# nrf52_watch_rev_0_9.net
KiCad netlist of a schematic drawn in EAGLE
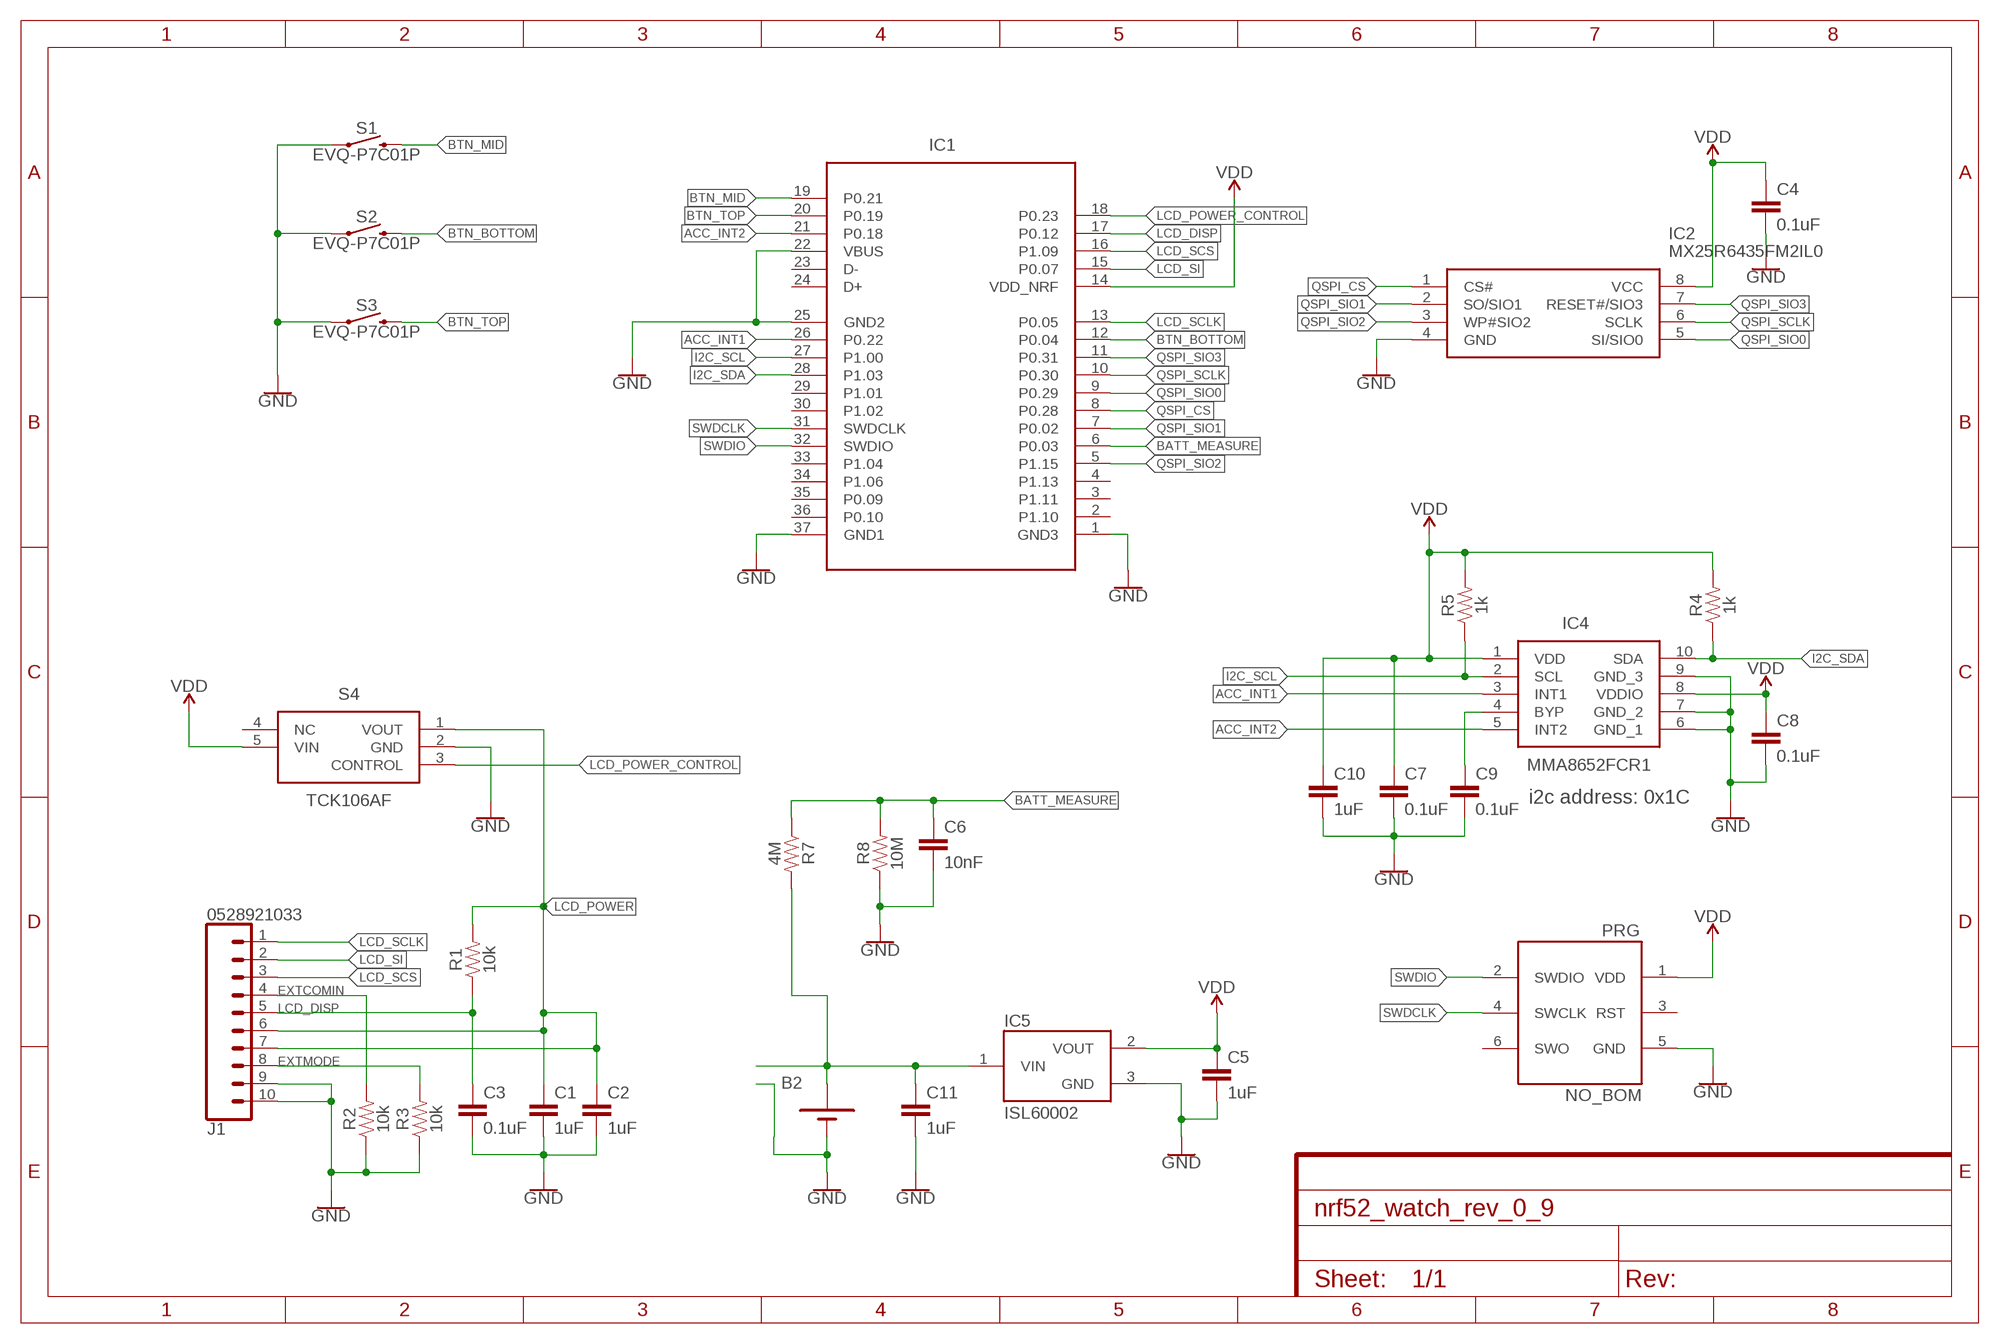
[diagram p0: schematic, sheet 1]

(export (version "E")
  (design (tool "Eeschema 10.0.6"))
  (components
    (comp (ref "B2")
      (value "BATTERY-BK-916")
      (footprint "eagle-import:BK-916-TR")
      (fields (field (name "MANUFACTURER_PART_NUMBER") "BK-916-TR"))
      (libsource (lib "eagle-import") (part "BATTERY-BK-916"))
    )
    (comp (ref "C1")
      (value "1uF")
      (footprint "eagle-import:C0402")
      (libsource (lib "eagle-import") (part "CAP-6.3V-20%-0402"))
    )
    (comp (ref "C2")
      (value "1uF")
      (footprint "eagle-import:C0402")
      (libsource (lib "eagle-import") (part "CAP-6.3V-20%-0402"))
    )
    (comp (ref "C3")
      (value "0.1uF")
      (footprint "eagle-import:C0402")
      (libsource (lib "eagle-import") (part "CAP-6.3V-20%-0402"))
    )
    (comp (ref "C4")
      (value "0.1uF")
      (footprint "eagle-import:C0402")
      (libsource (lib "eagle-import") (part "CAP-6.3V-20%-0402"))
    )
    (comp (ref "C5")
      (value "1uF")
      (footprint "eagle-import:C0402")
      (libsource (lib "eagle-import") (part "CAP-6.3V-20%-0402"))
    )
    (comp (ref "C6")
      (value "10nF")
      (footprint "eagle-import:C0402")
      (libsource (lib "eagle-import") (part "CAP-6.3V-20%-0402"))
    )
    (comp (ref "C7")
      (value "0.1uF")
      (footprint "eagle-import:C0402")
      (libsource (lib "eagle-import") (part "CAP-6.3V-20%-0402"))
    )
    (comp (ref "C8")
      (value "0.1uF")
      (footprint "eagle-import:C0402")
      (libsource (lib "eagle-import") (part "CAP-6.3V-20%-0402"))
    )
    (comp (ref "C9")
      (value "0.1uF")
      (footprint "eagle-import:C0402")
      (libsource (lib "eagle-import") (part "CAP-6.3V-20%-0402"))
    )
    (comp (ref "C10")
      (value "1uF")
      (footprint "eagle-import:C0402")
      (libsource (lib "eagle-import") (part "CAP-6.3V-20%-0402"))
    )
    (comp (ref "C11")
      (value "1uF")
      (footprint "eagle-import:C0402")
      (libsource (lib "eagle-import") (part "CAP-6.3V-20%-0402"))
    )
    (comp (ref "IC1")
      (value "HOLYIOT_18010")
      (footprint "eagle-import:HOLYIOT_18010_REDUCED")
      (fields (field (name "MANUFACTURER_PART_NUMBER") "18010"))
      (libsource (lib "eagle-import") (part "HOLYIOT_18010"))
    )
    (comp (ref "IC2")
      (value "MX25R6435FM2IL0")
      (footprint "eagle-import:SOIC127P790X216-8N")
      (fields (field (name "RS_PART_NUMBER") "1703108"))
      (libsource (lib "eagle-import") (part "MX25R6435FM2IL0"))
    )
    (comp (ref "IC4")
      (value "MMA8652FCR1")
      (footprint "eagle-import:SON40P200X200X100-10N")
      (fields (field (name "RS_PART_NUMBER") "8016889P"))
      (libsource (lib "eagle-import") (part "MMA8652FCR1"))
    )
    (comp (ref "IC5")
      (value "ISL60002")
      (footprint "eagle-import:SOT23-3")
      (libsource (lib "eagle-import") (part "ISL60002"))
    )
    (comp (ref "J1")
      (value "0528921033")
      (footprint "eagle-import:0528921033")
      (libsource (lib "eagle-import") (part "0528921033"))
    )
    (comp (ref "PRG")
      (value "NO_BOM")
      (footprint "eagle-import:1X06_1.27MM")
      (libsource (lib "eagle-import") (part "SWD_PROG_POGO"))
    )
    (comp (ref "R1")
      (value "10k")
      (footprint "eagle-import:R0402")
      (libsource (lib "eagle-import") (part "RES-0.063W-5%-0402"))
    )
    (comp (ref "R2")
      (value "10k")
      (footprint "eagle-import:R0402")
      (libsource (lib "eagle-import") (part "RES-0.063W-5%-0402"))
    )
    (comp (ref "R3")
      (value "10k")
      (footprint "eagle-import:R0402")
      (libsource (lib "eagle-import") (part "RES-0.063W-5%-0402"))
    )
    (comp (ref "R4")
      (value "1k")
      (footprint "eagle-import:R0402")
      (libsource (lib "eagle-import") (part "RES-0.063W-5%-0402"))
    )
    (comp (ref "R5")
      (value "1k")
      (footprint "eagle-import:R0402")
      (libsource (lib "eagle-import") (part "RES-0.063W-5%-0402"))
    )
    (comp (ref "R7")
      (value "4M")
      (footprint "eagle-import:R0402")
      (libsource (lib "eagle-import") (part "RES-0.063W-1%-0402"))
    )
    (comp (ref "R8")
      (value "10M")
      (footprint "eagle-import:R0402")
      (libsource (lib "eagle-import") (part "RES-0.063W-1%-0402"))
    )
    (comp (ref "S1")
      (value "EVQ-P7C01P")
      (footprint "eagle-import:EVQP7C01P")
      (fields (field (name "RS_PART_NUMBER") "8113353"))
      (libsource (lib "eagle-import") (part "EVQ-P7C01P"))
    )
    (comp (ref "S2")
      (value "EVQ-P7C01P")
      (footprint "eagle-import:EVQP7C01P")
      (fields (field (name "RS_PART_NUMBER") "8113353"))
      (libsource (lib "eagle-import") (part "EVQ-P7C01P"))
    )
    (comp (ref "S3")
      (value "EVQ-P7C01P")
      (footprint "eagle-import:EVQP7C01P")
      (fields (field (name "RS_PART_NUMBER") "8113353"))
      (libsource (lib "eagle-import") (part "EVQ-P7C01P"))
    )
    (comp (ref "S4")
      (value "TCK106AF")
      (footprint "eagle-import:SOT-25")
      (libsource (lib "eagle-import") (part "TCK106AF"))
    )
  )
  (nets
    (net (code "1") (name "/EXTCOMIN") (class "Default")
      (node (ref "J1") (pin "4") (pinfunction "4_4") (pintype "passive"))
      (node (ref "R2") (pin "2") (pinfunction "2_2") (pintype "passive"))
    )
    (net (code "2") (name "/EXTMODE") (class "Default")
      (node (ref "J1") (pin "8") (pinfunction "8_8") (pintype "passive"))
      (node (ref "R3") (pin "2") (pinfunction "2_2") (pintype "passive"))
    )
    (net (code "3") (name "ACC_INT1") (class "Default")
      (node (ref "IC1") (pin "26") (pinfunction "P0.22_26") (pintype "bidirectional"))
      (node (ref "IC4") (pin "3") (pinfunction "INT1_3") (pintype "bidirectional"))
    )
    (net (code "4") (name "ACC_INT2") (class "Default")
      (node (ref "IC1") (pin "21") (pinfunction "P0.18_21") (pintype "bidirectional"))
      (node (ref "IC4") (pin "5") (pinfunction "INT2_5") (pintype "bidirectional"))
    )
    (net (code "5") (name "BATT_MEASURE") (class "Default")
      (node (ref "C6") (pin "1") (pinfunction "1_1") (pintype "passive"))
      (node (ref "IC1") (pin "6") (pinfunction "P0.03_6") (pintype "bidirectional"))
      (node (ref "R7") (pin "1") (pinfunction "1_1") (pintype "passive"))
      (node (ref "R8") (pin "2") (pinfunction "2_2") (pintype "passive"))
    )
    (net (code "6") (name "BTN_BOTTOM") (class "Default")
      (node (ref "IC1") (pin "12") (pinfunction "P0.04_12") (pintype "bidirectional"))
      (node (ref "S2") (pin "1") (pinfunction "2_1") (pintype "passive"))
      (node (ref "S2") (pin "4") (pinfunction "2_4") (pintype "passive"))
    )
    (net (code "7") (name "BTN_MID") (class "Default")
      (node (ref "IC1") (pin "19") (pinfunction "P0.21_19") (pintype "bidirectional"))
      (node (ref "S1") (pin "1") (pinfunction "2_1") (pintype "passive"))
      (node (ref "S1") (pin "4") (pinfunction "2_4") (pintype "passive"))
    )
    (net (code "8") (name "BTN_TOP") (class "Default")
      (node (ref "IC1") (pin "20") (pinfunction "P0.19_20") (pintype "bidirectional"))
      (node (ref "S3") (pin "1") (pinfunction "2_1") (pintype "passive"))
      (node (ref "S3") (pin "4") (pinfunction "2_4") (pintype "passive"))
    )
    (net (code "9") (name "GND") (class "Default")
      (node (ref "B2") (pin "N") (pinfunction "-_N") (pintype "power_in"))
      (node (ref "C1") (pin "2") (pinfunction "2_2") (pintype "passive"))
      (node (ref "C10") (pin "2") (pinfunction "2_2") (pintype "passive"))
      (node (ref "C11") (pin "2") (pinfunction "2_2") (pintype "passive"))
      (node (ref "C2") (pin "2") (pinfunction "2_2") (pintype "passive"))
      (node (ref "C3") (pin "2") (pinfunction "2_2") (pintype "passive"))
      (node (ref "C4") (pin "2") (pinfunction "2_2") (pintype "passive"))
      (node (ref "C5") (pin "2") (pinfunction "2_2") (pintype "passive"))
      (node (ref "C6") (pin "2") (pinfunction "2_2") (pintype "passive"))
      (node (ref "C7") (pin "2") (pinfunction "2_2") (pintype "passive"))
      (node (ref "C8") (pin "2") (pinfunction "2_2") (pintype "passive"))
      (node (ref "C9") (pin "2") (pinfunction "2_2") (pintype "passive"))
      (node (ref "IC1") (pin "1") (pinfunction "GND3_1") (pintype "bidirectional"))
      (node (ref "IC1") (pin "22") (pinfunction "VBUS_22") (pintype "bidirectional"))
      (node (ref "IC1") (pin "25") (pinfunction "GND2_25") (pintype "bidirectional"))
      (node (ref "IC1") (pin "37") (pinfunction "GND1_37") (pintype "bidirectional"))
      (node (ref "IC2") (pin "4") (pinfunction "GND_4") (pintype "bidirectional"))
      (node (ref "IC4") (pin "6") (pinfunction "GND_1_6") (pintype "bidirectional"))
      (node (ref "IC4") (pin "7") (pinfunction "GND_2_7") (pintype "bidirectional"))
      (node (ref "IC4") (pin "9") (pinfunction "GND_3_9") (pintype "bidirectional"))
      (node (ref "IC5") (pin "3") (pinfunction "GND_3") (pintype "bidirectional"))
      (node (ref "J1") (pin "10") (pinfunction "10_10") (pintype "passive"))
      (node (ref "J1") (pin "9") (pinfunction "9_9") (pintype "passive"))
      (node (ref "PRG") (pin "5") (pinfunction "GND_5") (pintype "bidirectional"))
      (node (ref "R2") (pin "1") (pinfunction "1_1") (pintype "passive"))
      (node (ref "R3") (pin "1") (pinfunction "1_1") (pintype "passive"))
      (node (ref "R8") (pin "1") (pinfunction "1_1") (pintype "passive"))
      (node (ref "S1") (pin "2") (pinfunction "1_2") (pintype "passive"))
      (node (ref "S1") (pin "3") (pinfunction "1_3") (pintype "passive"))
      (node (ref "S2") (pin "2") (pinfunction "1_2") (pintype "passive"))
      (node (ref "S2") (pin "3") (pinfunction "1_3") (pintype "passive"))
      (node (ref "S3") (pin "2") (pinfunction "1_2") (pintype "passive"))
      (node (ref "S3") (pin "3") (pinfunction "1_3") (pintype "passive"))
      (node (ref "S4") (pin "2") (pinfunction "GND_2") (pintype "passive"))
    )
    (net (code "10") (name "I2C_SCL") (class "Default")
      (node (ref "IC1") (pin "27") (pinfunction "P1.00_27") (pintype "bidirectional"))
      (node (ref "IC4") (pin "2") (pinfunction "SCL_2") (pintype "bidirectional"))
      (node (ref "R5") (pin "1") (pinfunction "1_1") (pintype "passive"))
    )
    (net (code "11") (name "I2C_SDA") (class "Default")
      (node (ref "IC1") (pin "28") (pinfunction "P1.03_28") (pintype "bidirectional"))
      (node (ref "IC4") (pin "10") (pinfunction "SDA_10") (pintype "bidirectional"))
      (node (ref "R4") (pin "1") (pinfunction "1_1") (pintype "passive"))
    )
    (net (code "12") (name "LCD_DISP") (class "Default")
      (node (ref "C3") (pin "1") (pinfunction "1_1") (pintype "passive"))
      (node (ref "IC1") (pin "17") (pinfunction "P0.12_17") (pintype "bidirectional"))
      (node (ref "J1") (pin "5") (pinfunction "5_5") (pintype "passive"))
      (node (ref "R1") (pin "1") (pinfunction "1_1") (pintype "passive"))
    )
    (net (code "13") (name "LCD_POWER") (class "Default")
      (node (ref "C1") (pin "1") (pinfunction "1_1") (pintype "passive"))
      (node (ref "C2") (pin "1") (pinfunction "1_1") (pintype "passive"))
      (node (ref "J1") (pin "6") (pinfunction "6_6") (pintype "passive"))
      (node (ref "J1") (pin "7") (pinfunction "7_7") (pintype "passive"))
      (node (ref "R1") (pin "2") (pinfunction "2_2") (pintype "passive"))
      (node (ref "S4") (pin "1") (pinfunction "VOUT_1") (pintype "passive"))
    )
    (net (code "14") (name "LCD_POWER_CONTROL") (class "Default")
      (node (ref "IC1") (pin "18") (pinfunction "P0.23_18") (pintype "bidirectional"))
      (node (ref "S4") (pin "3") (pinfunction "CONTROL_3") (pintype "passive"))
    )
    (net (code "15") (name "LCD_SCLK") (class "Default")
      (node (ref "IC1") (pin "13") (pinfunction "P0.05_13") (pintype "bidirectional"))
      (node (ref "J1") (pin "1") (pinfunction "1_1") (pintype "passive"))
    )
    (net (code "16") (name "LCD_SCS") (class "Default")
      (node (ref "IC1") (pin "16") (pinfunction "P1.09_16") (pintype "bidirectional"))
      (node (ref "J1") (pin "3") (pinfunction "3_3") (pintype "passive"))
    )
    (net (code "17") (name "LCD_SI") (class "Default")
      (node (ref "IC1") (pin "15") (pinfunction "P0.07_15") (pintype "bidirectional"))
      (node (ref "J1") (pin "2") (pinfunction "2_2") (pintype "passive"))
    )
    (net (code "18") (name "Net-(IC4-BYP)") (class "Default")
      (node (ref "C9") (pin "1") (pinfunction "1_1") (pintype "passive"))
      (node (ref "IC4") (pin "4") (pinfunction "BYP_4") (pintype "bidirectional"))
    )
    (net (code "19") (name "Net-(IC5-VIN)") (class "Default")
      (node (ref "B2") (pin "P1") (pinfunction "+_P1") (pintype "power_in"))
      (node (ref "B2") (pin "P2") (pinfunction "+_P2") (pintype "power_in"))
      (node (ref "C11") (pin "1") (pinfunction "1_1") (pintype "passive"))
      (node (ref "IC5") (pin "1") (pinfunction "VIN_1") (pintype "bidirectional"))
      (node (ref "R7") (pin "2") (pinfunction "2_2") (pintype "passive"))
    )
    (net (code "20") (name "QSPI_CS") (class "Default")
      (node (ref "IC1") (pin "8") (pinfunction "P0.28_8") (pintype "bidirectional"))
      (node (ref "IC2") (pin "1") (pinfunction "CS#_1") (pintype "bidirectional"))
    )
    (net (code "21") (name "QSPI_SCLK") (class "Default")
      (node (ref "IC1") (pin "10") (pinfunction "P0.30_10") (pintype "bidirectional"))
      (node (ref "IC2") (pin "6") (pinfunction "SCLK_6") (pintype "bidirectional"))
    )
    (net (code "22") (name "QSPI_SIO0") (class "Default")
      (node (ref "IC1") (pin "9") (pinfunction "P0.29_9") (pintype "bidirectional"))
      (node (ref "IC2") (pin "5") (pinfunction "SI/SIO0_5") (pintype "bidirectional"))
    )
    (net (code "23") (name "QSPI_SIO1") (class "Default")
      (node (ref "IC1") (pin "7") (pinfunction "P0.02_7") (pintype "bidirectional"))
      (node (ref "IC2") (pin "2") (pinfunction "SO/SIO1_2") (pintype "bidirectional"))
    )
    (net (code "24") (name "QSPI_SIO2") (class "Default")
      (node (ref "IC1") (pin "5") (pinfunction "P1.15_5") (pintype "bidirectional"))
      (node (ref "IC2") (pin "3") (pinfunction "WP#SIO2_3") (pintype "bidirectional"))
    )
    (net (code "25") (name "QSPI_SIO3") (class "Default")
      (node (ref "IC1") (pin "11") (pinfunction "P0.31_11") (pintype "bidirectional"))
      (node (ref "IC2") (pin "7") (pinfunction "RESET#/SIO3_7") (pintype "bidirectional"))
    )
    (net (code "26") (name "SWDCLK") (class "Default")
      (node (ref "IC1") (pin "31") (pinfunction "SWDCLK_31") (pintype "bidirectional"))
      (node (ref "PRG") (pin "4") (pinfunction "SWCLK_4") (pintype "bidirectional"))
    )
    (net (code "27") (name "SWDIO") (class "Default")
      (node (ref "IC1") (pin "32") (pinfunction "SWDIO_32") (pintype "bidirectional"))
      (node (ref "PRG") (pin "2") (pinfunction "SWDIO_2") (pintype "bidirectional"))
    )
    (net (code "28") (name "VDD") (class "Default")
      (node (ref "C10") (pin "1") (pinfunction "1_1") (pintype "passive"))
      (node (ref "C4") (pin "1") (pinfunction "1_1") (pintype "passive"))
      (node (ref "C5") (pin "1") (pinfunction "1_1") (pintype "passive"))
      (node (ref "C7") (pin "1") (pinfunction "1_1") (pintype "passive"))
      (node (ref "C8") (pin "1") (pinfunction "1_1") (pintype "passive"))
      (node (ref "IC1") (pin "14") (pinfunction "VDD_NRF_14") (pintype "bidirectional"))
      (node (ref "IC2") (pin "8") (pinfunction "VCC_8") (pintype "bidirectional"))
      (node (ref "IC4") (pin "1") (pinfunction "VDD_1") (pintype "bidirectional"))
      (node (ref "IC4") (pin "8") (pinfunction "VDDIO_8") (pintype "bidirectional"))
      (node (ref "IC5") (pin "2") (pinfunction "VOUT_2") (pintype "bidirectional"))
      (node (ref "PRG") (pin "1") (pinfunction "VDD_1") (pintype "bidirectional"))
      (node (ref "R4") (pin "2") (pinfunction "2_2") (pintype "passive"))
      (node (ref "R5") (pin "2") (pinfunction "2_2") (pintype "passive"))
      (node (ref "S4") (pin "5") (pinfunction "VIN_5") (pintype "passive"))
    )
    (net (code "29") (name "unconnected-(IC1-D+-Pad24)") (class "Default")
      (node (ref "IC1") (pin "24") (pinfunction "D+_24") (pintype "bidirectional"))
    )
    (net (code "30") (name "unconnected-(IC1-D--Pad23)") (class "Default")
      (node (ref "IC1") (pin "23") (pinfunction "D-_23") (pintype "bidirectional"))
    )
    (net (code "31") (name "unconnected-(IC1-P0.09-Pad35)") (class "Default")
      (node (ref "IC1") (pin "35") (pinfunction "P0.09_35") (pintype "bidirectional"))
    )
    (net (code "32") (name "unconnected-(IC1-P0.10-Pad36)") (class "Default")
      (node (ref "IC1") (pin "36") (pinfunction "P0.10_36") (pintype "bidirectional"))
    )
    (net (code "33") (name "unconnected-(IC1-P1.01-Pad29)") (class "Default")
      (node (ref "IC1") (pin "29") (pinfunction "P1.01_29") (pintype "bidirectional"))
    )
    (net (code "34") (name "unconnected-(IC1-P1.02-Pad30)") (class "Default")
      (node (ref "IC1") (pin "30") (pinfunction "P1.02_30") (pintype "bidirectional"))
    )
    (net (code "35") (name "unconnected-(IC1-P1.04-Pad33)") (class "Default")
      (node (ref "IC1") (pin "33") (pinfunction "P1.04_33") (pintype "bidirectional"))
    )
    (net (code "36") (name "unconnected-(IC1-P1.06-Pad34)") (class "Default")
      (node (ref "IC1") (pin "34") (pinfunction "P1.06_34") (pintype "bidirectional"))
    )
    (net (code "37") (name "unconnected-(IC1-P1.10-Pad2)") (class "Default")
      (node (ref "IC1") (pin "2") (pinfunction "P1.10_2") (pintype "bidirectional"))
    )
    (net (code "38") (name "unconnected-(IC1-P1.11-Pad3)") (class "Default")
      (node (ref "IC1") (pin "3") (pinfunction "P1.11_3") (pintype "bidirectional"))
    )
    (net (code "39") (name "unconnected-(IC1-P1.13-Pad4)") (class "Default")
      (node (ref "IC1") (pin "4") (pinfunction "P1.13_4") (pintype "bidirectional"))
    )
    (net (code "40") (name "unconnected-(PRG-RST-Pad3)") (class "Default")
      (node (ref "PRG") (pin "3") (pinfunction "RST_3") (pintype "bidirectional"))
    )
    (net (code "41") (name "unconnected-(PRG-SWO-Pad6)") (class "Default")
      (node (ref "PRG") (pin "6") (pinfunction "SWO_6") (pintype "bidirectional"))
    )
    (net (code "42") (name "unconnected-(S4-NC-Pad4)") (class "Default")
      (node (ref "S4") (pin "4") (pinfunction "NC_4") (pintype "no_connect"))
    )
  )
)
